# SCH_NFC-Business-Tag_2024-09-03.net
KiCad netlist of a schematic drawn in EasyEDA
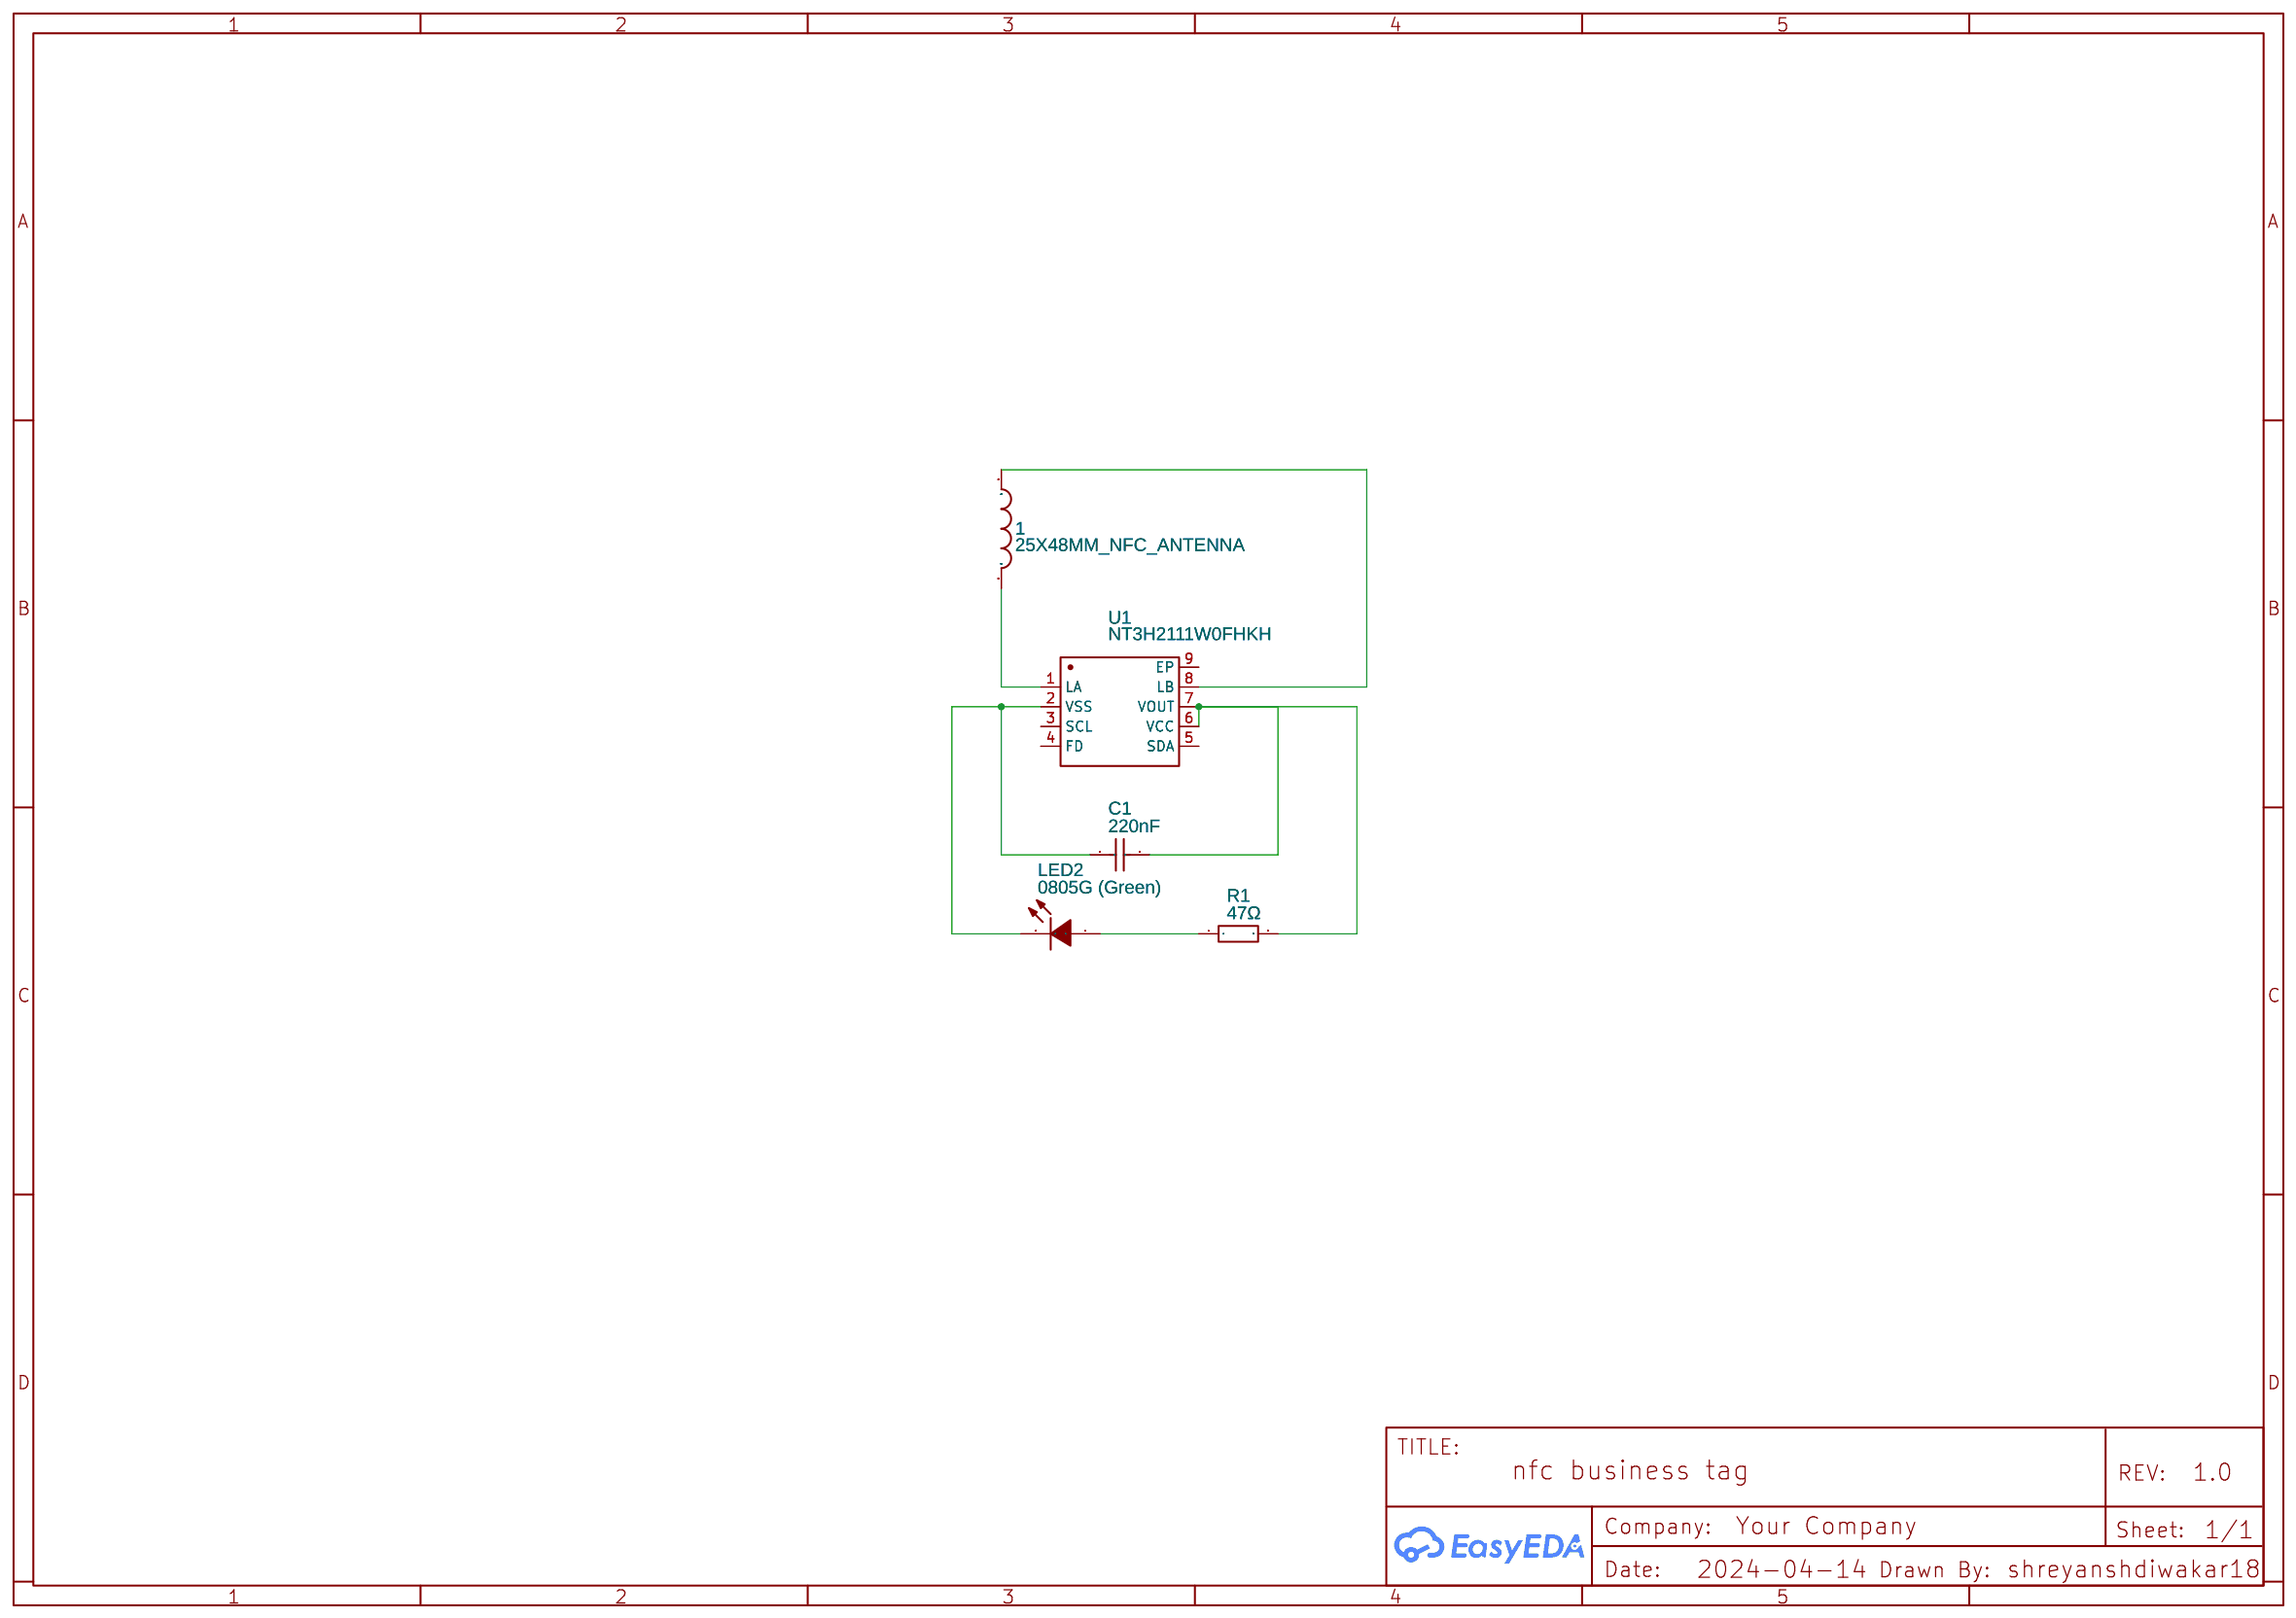
[diagram p0: schematic sheet]

(export (version "E")
  (design (tool "Eeschema 10.0.6"))
  (components
    (comp (ref "1") (value "25X48MM_NFC_ANTENNA") (libsource (lib "") (part "25X48MM_NFC_ANTENNA")))
    (comp (ref "C1")
      (value "220nF")
      (fields
        (field (name "Manufacturer Part") "CL10B224KA8NNNC")
        (field (name "Manufacturer") "SAMSUNG(三星)")
      )
      (libsource (lib "") (part "CL10B224KA8NNNC"))
    )
    (comp (ref "LED2")
      (value "0805G (Green)")
      (fields (field (name "Manufacturer Part") "KT-0805G") (field (name "Manufacturer") "KENTO"))
      (libsource (lib "") (part "0805G (Green)"))
    )
    (comp (ref "R1")
      (value "47Ω")
      (fields
        (field (name "Manufacturer Part") "0603WAF470JT5E")
        (field (name "Manufacturer") "UNI-ROYAL(厚声)")
      )
      (libsource (lib "") (part "0603WAF470JT5E"))
    )
    (comp (ref "U1")
      (value "NT3H2111W0FHKH")
      (fields (field (name "Manufacturer") "NXP(恩智浦)"))
      (libsource (lib "") (part "NT3H2111W0FHKH"))
    )
  )
  (nets
    (net (code "1") (name "Net-(LED2-A)") (class "Default")
      (node (ref "LED2") (pin "1") (pinfunction "A_1") (pintype "unspecified"))
      (node (ref "R1") (pin "1") (pinfunction "1_1") (pintype "input"))
    )
    (net (code "2") (name "Net-(LED2-K)") (class "Default")
      (node (ref "C1") (pin "1") (pinfunction "1_1") (pintype "input"))
      (node (ref "LED2") (pin "2") (pinfunction "K_2") (pintype "unspecified"))
      (node (ref "U1") (pin "2") (pinfunction "VSS_2") (pintype "unspecified"))
    )
    (net (code "3") (name "Net-(U1-LA)") (class "Default")
      (node (ref "1") (pin "P$2") (pinfunction "P$2_P$2") (pintype "bidirectional"))
      (node (ref "U1") (pin "1") (pinfunction "LA_1") (pintype "unspecified"))
    )
    (net (code "4") (name "Net-(U1-LB)") (class "Default")
      (node (ref "1") (pin "P$1") (pinfunction "P$1_P$1") (pintype "bidirectional"))
      (node (ref "U1") (pin "8") (pinfunction "LB_8") (pintype "unspecified"))
    )
    (net (code "5") (name "Net-(U1-VCC)") (class "Default")
      (node (ref "C1") (pin "2") (pinfunction "2_2") (pintype "input"))
      (node (ref "R1") (pin "2") (pinfunction "2_2") (pintype "input"))
      (node (ref "U1") (pin "6") (pinfunction "VCC_6") (pintype "unspecified"))
      (node (ref "U1") (pin "7") (pinfunction "VOUT_7") (pintype "unspecified"))
    )
    (net (code "6") (name "unconnected-(U1-EP-Pad9)") (class "Default")
      (node (ref "U1") (pin "9") (pinfunction "EP_9") (pintype "unspecified"))
    )
    (net (code "7") (name "unconnected-(U1-FD-Pad4)") (class "Default")
      (node (ref "U1") (pin "4") (pinfunction "FD_4") (pintype "unspecified"))
    )
    (net (code "8") (name "unconnected-(U1-SCL-Pad3)") (class "Default")
      (node (ref "U1") (pin "3") (pinfunction "SCL_3") (pintype "unspecified"))
    )
    (net (code "9") (name "unconnected-(U1-SDA-Pad5)") (class "Default")
      (node (ref "U1") (pin "5") (pinfunction "SDA_5") (pintype "unspecified"))
    )
  )
)
